# VolRegModule.net
KiCad netlist of a schematic drawn in EAGLE
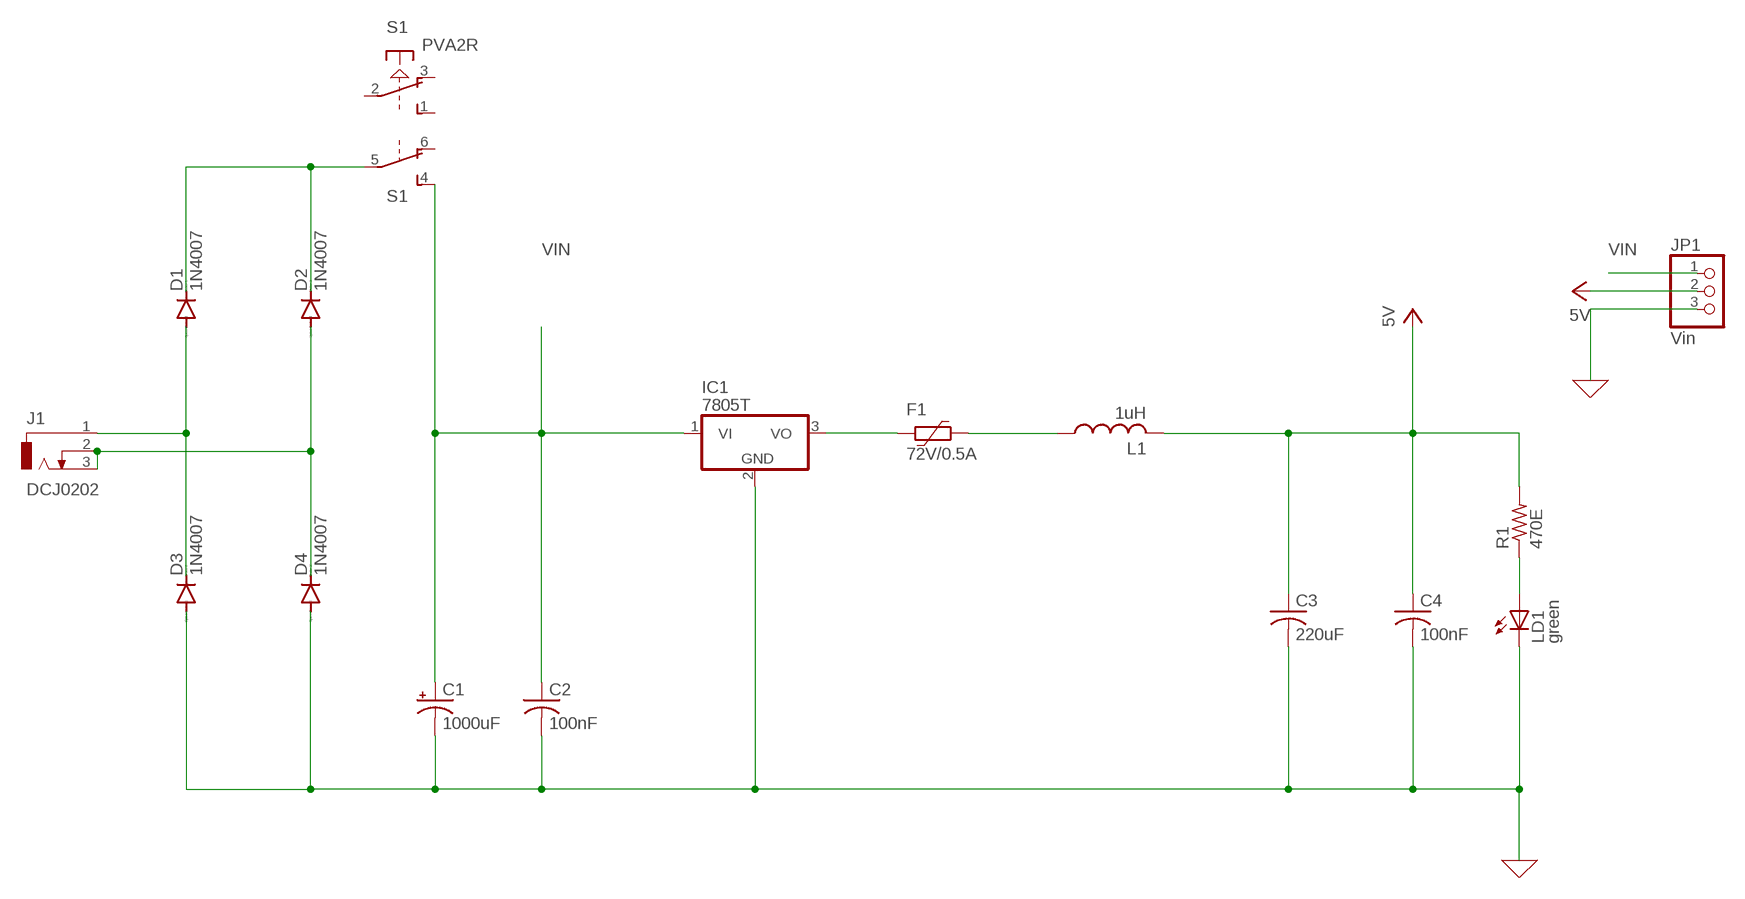
[diagram p0: schematic, sheet 1]

(export (version "E")
  (design (tool "Eeschema 10.0.6"))
  (components
    (comp (ref "C1")
      (value "1000uF")
      (footprint "eagle-import:E5-13")
      (libsource (lib "eagle-import") (part "CPOL-USE5-13"))
    )
    (comp (ref "C2")
      (value "100nF")
      (footprint "eagle-import:C0805")
      (libsource (lib "eagle-import") (part "C-USC0805"))
    )
    (comp (ref "C3")
      (value "220uF")
      (footprint "eagle-import:C0805")
      (libsource (lib "eagle-import") (part "C-USC0805"))
    )
    (comp (ref "C4")
      (value "100nF")
      (footprint "eagle-import:C0805")
      (libsource (lib "eagle-import") (part "C-USC0805"))
    )
    (comp (ref "D1")
      (value "1N4007")
      (footprint "eagle-import:DO41-10")
      (libsource (lib "eagle-import") (part "1N4004"))
    )
    (comp (ref "D2")
      (value "1N4007")
      (footprint "eagle-import:DO41-10")
      (libsource (lib "eagle-import") (part "1N4004"))
    )
    (comp (ref "D3")
      (value "1N4007")
      (footprint "eagle-import:DO41-10")
      (libsource (lib "eagle-import") (part "1N4004"))
    )
    (comp (ref "D4")
      (value "1N4007")
      (footprint "eagle-import:DO41-10")
      (libsource (lib "eagle-import") (part "1N4004"))
    )
    (comp (ref "F1")
      (value "72V/0.5A")
      (footprint "eagle-import:1812L")
      (fields (field (name "MF") "Littelfuse") (field (name "MPN") "1812L350SL"))
      (libsource (lib "eagle-import") (part "?1812L350SL"))
    )
    (comp (ref "IC1")
      (value "7805T")
      (footprint "eagle-import:TO220H")
      (libsource (lib "eagle-import") (part "78T05"))
    )
    (comp (ref "J1")
      (value "DCJ0202")
      (footprint "eagle-import:DCJ0202")
      (libsource (lib "eagle-import") (part "DCJ0202"))
    )
    (comp (ref "JP1")
      (value "Vin")
      (footprint "eagle-import:1X03")
      (libsource (lib "eagle-import") (part "PINHD-1X03_2.54"))
    )
    (comp (ref "L1")
      (value "1uH")
      (footprint "eagle-import:L0805")
      (libsource (lib "eagle-import") (part "L-USL0805"))
    )
    (comp (ref "LD1")
      (value "green")
      (footprint "eagle-import:CHIP-LED0805")
      (libsource (lib "eagle-import") (part "LEDCHIP-LED0805"))
    )
    (comp (ref "R1")
      (value "470E")
      (footprint "eagle-import:R0805")
      (libsource (lib "eagle-import") (part "R-US_R0805"))
    )
    (comp (ref "S1")
      (value "PVA2R")
      (footprint "eagle-import:PVA2R")
      (libsource (lib "eagle-import") (part "PVA2R"))
    )
  )
  (nets
    (net (code "1") (name "/VIN") (class "Default")
      (node (ref "C1") (pin "+") (pinfunction "+_+") (pintype "passive"))
      (node (ref "C2") (pin "1") (pinfunction "1_1") (pintype "passive"))
      (node (ref "IC1") (pin "1") (pinfunction "VI_1") (pintype "input"))
      (node (ref "JP1") (pin "1") (pinfunction "1_1") (pintype "passive"))
      (node (ref "S1") (pin "4") (pinfunction "S_4") (pintype "passive"))
    )
    (net (code "2") (name "5V") (class "Default")
      (node (ref "C3") (pin "1") (pinfunction "1_1") (pintype "passive"))
      (node (ref "C4") (pin "1") (pinfunction "1_1") (pintype "passive"))
      (node (ref "JP1") (pin "2") (pinfunction "2_2") (pintype "passive"))
      (node (ref "L1") (pin "2") (pinfunction "2_2") (pintype "passive"))
      (node (ref "R1") (pin "2") (pinfunction "2_2") (pintype "passive"))
    )
    (net (code "3") (name "GND") (class "Default")
      (node (ref "C1") (pin "-") (pinfunction "-_-") (pintype "passive"))
      (node (ref "C2") (pin "2") (pinfunction "2_2") (pintype "passive"))
      (node (ref "C3") (pin "2") (pinfunction "2_2") (pintype "passive"))
      (node (ref "C4") (pin "2") (pinfunction "2_2") (pintype "passive"))
      (node (ref "D3") (pin "A") (pinfunction "A_A") (pintype "passive"))
      (node (ref "D4") (pin "A") (pinfunction "A_A") (pintype "passive"))
      (node (ref "IC1") (pin "2") (pinfunction "GND_2") (pintype "passive"))
      (node (ref "JP1") (pin "3") (pinfunction "3_3") (pintype "passive"))
      (node (ref "LD1") (pin "C") (pinfunction "C_C") (pintype "passive"))
    )
    (net (code "4") (name "Net-(D1-PadA)") (class "Default")
      (node (ref "D1") (pin "A") (pinfunction "A_A") (pintype "passive"))
      (node (ref "D3") (pin "C") (pinfunction "C_C") (pintype "passive"))
      (node (ref "J1") (pin "1") (pinfunction "1_1") (pintype "passive"))
    )
    (net (code "5") (name "Net-(D2-PadA)") (class "Default")
      (node (ref "D2") (pin "A") (pinfunction "A_A") (pintype "passive"))
      (node (ref "D4") (pin "C") (pinfunction "C_C") (pintype "passive"))
      (node (ref "J1") (pin "2") (pinfunction "2_2") (pintype "passive"))
      (node (ref "J1") (pin "3") (pinfunction "3_3") (pintype "passive"))
    )
    (net (code "6") (name "Net-(F1-Pad1)") (class "Default")
      (node (ref "F1") (pin "1") (pinfunction "1_1") (pintype "passive"))
      (node (ref "L1") (pin "1") (pinfunction "1_1") (pintype "passive"))
    )
    (net (code "7") (name "Net-(IC1-VO)") (class "Default")
      (node (ref "F1") (pin "2") (pinfunction "2_2") (pintype "passive"))
      (node (ref "IC1") (pin "3") (pinfunction "VO_3") (pintype "passive"))
    )
    (net (code "8") (name "Net-(LD1-PadA)") (class "Default")
      (node (ref "LD1") (pin "A") (pinfunction "A_A") (pintype "passive"))
      (node (ref "R1") (pin "1") (pinfunction "1_1") (pintype "passive"))
    )
    (net (code "9") (name "Net-(S1B-P)") (class "Default")
      (node (ref "D1") (pin "C") (pinfunction "C_C") (pintype "passive"))
      (node (ref "D2") (pin "C") (pinfunction "C_C") (pintype "passive"))
      (node (ref "S1") (pin "5") (pinfunction "P_5") (pintype "passive"))
    )
    (net (code "10") (name "unconnected-(S1A-O-Pad3)") (class "Default")
      (node (ref "S1") (pin "3") (pinfunction "O_3") (pintype "passive"))
    )
    (net (code "11") (name "unconnected-(S1A-P-Pad2)") (class "Default")
      (node (ref "S1") (pin "2") (pinfunction "P_2") (pintype "passive"))
    )
    (net (code "12") (name "unconnected-(S1A-S-Pad1)") (class "Default")
      (node (ref "S1") (pin "1") (pinfunction "S_1") (pintype "passive"))
    )
    (net (code "13") (name "unconnected-(S1B-O-Pad6)") (class "Default")
      (node (ref "S1") (pin "6") (pinfunction "O_6") (pintype "passive"))
    )
  )
)
